# tank_motor_control.net
KiCad netlist of a schematic drawn in EAGLE
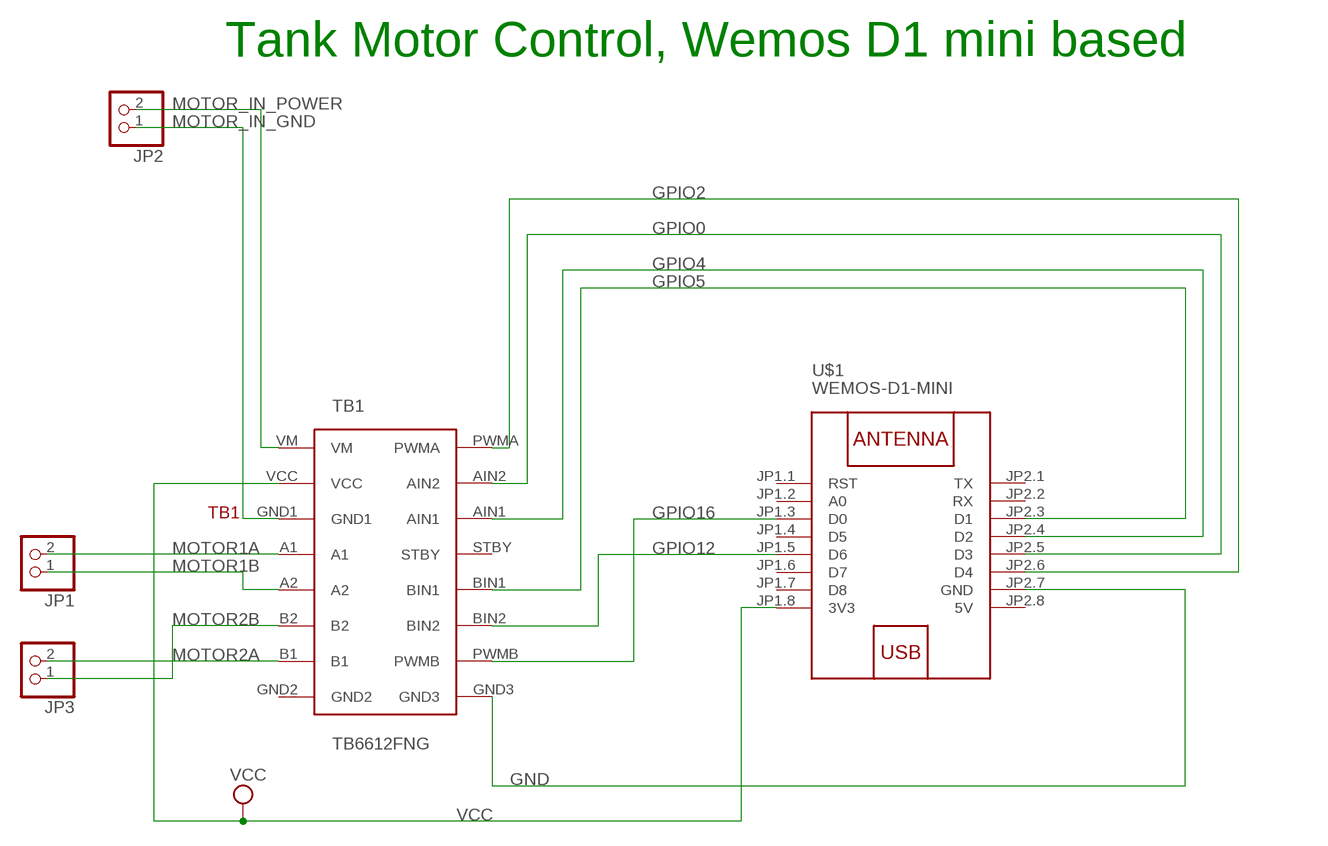
[diagram p0: schematic, sheet 1]

(export (version "E")
  (design (tool "Eeschema 10.0.6"))
  (components
    (comp (ref "JP1")
      (value "PINHD-1X2/90")
      (footprint "eagle-import:1X02_90")
      (libsource (lib "eagle-import") (part "PINHD-1X2/90"))
    )
    (comp (ref "JP2")
      (value "PINHD-1X2/90")
      (footprint "eagle-import:1X02_90")
      (libsource (lib "eagle-import") (part "PINHD-1X2/90"))
    )
    (comp (ref "JP3")
      (value "PINHD-1X2/90")
      (footprint "eagle-import:1X02_90")
      (libsource (lib "eagle-import") (part "PINHD-1X2/90"))
    )
    (comp (ref "TB1")
      (value "TB6612FNG")
      (footprint "eagle-import:TB6612FNG")
      (libsource (lib "eagle-import") (part "TB6612FNG"))
    )
    (comp (ref "U$1")
      (value "WEMOS-D1-MINI")
      (footprint "eagle-import:WEMOS-D1-MINI")
      (libsource (lib "eagle-import") (part "WEMOS-D1-MINI"))
    )
  )
  (nets
    (net (code "1") (name "/5V") (class "Default")
      (node (ref "U$1") (pin "JP2.8") (pinfunction "5V_JP2.8") (pintype "power_in"))
    )
    (net (code "2") (name "/GND") (class "Default")
      (node (ref "TB1") (pin "GND3") (pinfunction "GND3_GND3") (pintype "bidirectional"))
      (node (ref "U$1") (pin "JP2.7") (pinfunction "GND_JP2.7") (pintype "power_in"))
    )
    (net (code "3") (name "/GPIO0") (class "Default")
      (node (ref "TB1") (pin "AIN2") (pinfunction "AIN2_AIN2") (pintype "bidirectional"))
      (node (ref "U$1") (pin "JP2.5") (pinfunction "D3_JP2.5") (pintype "bidirectional"))
    )
    (net (code "4") (name "/GPIO2") (class "Default")
      (node (ref "TB1") (pin "PWMA") (pinfunction "PWMA_PWMA") (pintype "bidirectional"))
      (node (ref "U$1") (pin "JP2.6") (pinfunction "D4_JP2.6") (pintype "bidirectional"))
    )
    (net (code "5") (name "/GPIO4") (class "Default")
      (node (ref "TB1") (pin "AIN1") (pinfunction "AIN1_AIN1") (pintype "bidirectional"))
      (node (ref "U$1") (pin "JP2.4") (pinfunction "D2_JP2.4") (pintype "bidirectional"))
    )
    (net (code "6") (name "/GPIO5") (class "Default")
      (node (ref "TB1") (pin "BIN1") (pinfunction "BIN1_BIN1") (pintype "bidirectional"))
      (node (ref "U$1") (pin "JP2.3") (pinfunction "D1_JP2.3") (pintype "bidirectional"))
    )
    (net (code "7") (name "/GPIO12") (class "Default")
      (node (ref "TB1") (pin "BIN2") (pinfunction "BIN2_BIN2") (pintype "bidirectional"))
      (node (ref "U$1") (pin "JP1.5") (pinfunction "D6_JP1.5") (pintype "bidirectional"))
    )
    (net (code "8") (name "/GPIO16") (class "Default")
      (node (ref "TB1") (pin "PWMB") (pinfunction "PWMB_PWMB") (pintype "bidirectional"))
      (node (ref "U$1") (pin "JP1.3") (pinfunction "D0_JP1.3") (pintype "bidirectional"))
    )
    (net (code "9") (name "/MOTOR1A") (class "Default")
      (node (ref "JP1") (pin "2") (pinfunction "2_2") (pintype "passive"))
      (node (ref "TB1") (pin "A1") (pinfunction "A1_A1") (pintype "bidirectional"))
    )
    (net (code "10") (name "/MOTOR1B") (class "Default")
      (node (ref "JP1") (pin "1") (pinfunction "1_1") (pintype "passive"))
      (node (ref "TB1") (pin "A2") (pinfunction "A2_A2") (pintype "bidirectional"))
    )
    (net (code "11") (name "/MOTOR2A") (class "Default")
      (node (ref "JP3") (pin "2") (pinfunction "2_2") (pintype "passive"))
      (node (ref "TB1") (pin "B1") (pinfunction "B1_B1") (pintype "bidirectional"))
    )
    (net (code "12") (name "/MOTOR2B") (class "Default")
      (node (ref "JP3") (pin "1") (pinfunction "1_1") (pintype "passive"))
      (node (ref "TB1") (pin "B2") (pinfunction "B2_B2") (pintype "bidirectional"))
    )
    (net (code "13") (name "/MOTOR_IN_GND") (class "Default")
      (node (ref "JP2") (pin "1") (pinfunction "1_1") (pintype "passive"))
      (node (ref "TB1") (pin "GND1") (pinfunction "GND1_GND1") (pintype "bidirectional"))
    )
    (net (code "14") (name "/MOTOR_IN_POWER") (class "Default")
      (node (ref "JP2") (pin "2") (pinfunction "2_2") (pintype "passive"))
      (node (ref "TB1") (pin "VM") (pinfunction "VM_VM") (pintype "bidirectional"))
    )
    (net (code "15") (name "VCC") (class "Default")
      (node (ref "TB1") (pin "VCC") (pinfunction "VCC_VCC") (pintype "bidirectional"))
      (node (ref "U$1") (pin "JP1.8") (pinfunction "3V3_JP1.8") (pintype "power_in"))
    )
    (net (code "16") (name "unconnected-(TB1-PadGND2)") (class "Default")
      (node (ref "TB1") (pin "GND2") (pinfunction "GND2_GND2") (pintype "bidirectional"))
    )
    (net (code "17") (name "unconnected-(TB1-PadSTBY)") (class "Default")
      (node (ref "TB1") (pin "STBY") (pinfunction "STBY_STBY") (pintype "bidirectional"))
    )
    (net (code "18") (name "unconnected-(U$1-A0-PadJP1.2)") (class "Default")
      (node (ref "U$1") (pin "JP1.2") (pinfunction "A0_JP1.2") (pintype "bidirectional"))
    )
    (net (code "19") (name "unconnected-(U$1-D5-PadJP1.4)") (class "Default")
      (node (ref "U$1") (pin "JP1.4") (pinfunction "D5_JP1.4") (pintype "bidirectional"))
    )
    (net (code "20") (name "unconnected-(U$1-D7-PadJP1.6)") (class "Default")
      (node (ref "U$1") (pin "JP1.6") (pinfunction "D7_JP1.6") (pintype "bidirectional"))
    )
    (net (code "21") (name "unconnected-(U$1-D8-PadJP1.7)") (class "Default")
      (node (ref "U$1") (pin "JP1.7") (pinfunction "D8_JP1.7") (pintype "bidirectional"))
    )
    (net (code "22") (name "unconnected-(U$1-RST-PadJP1.1)") (class "Default")
      (node (ref "U$1") (pin "JP1.1") (pinfunction "RST_JP1.1") (pintype "bidirectional"))
    )
    (net (code "23") (name "unconnected-(U$1-RX-PadJP2.2)") (class "Default")
      (node (ref "U$1") (pin "JP2.2") (pinfunction "RX_JP2.2") (pintype "bidirectional"))
    )
    (net (code "24") (name "unconnected-(U$1-TX-PadJP2.1)") (class "Default")
      (node (ref "U$1") (pin "JP2.1") (pinfunction "TX_JP2.1") (pintype "bidirectional"))
    )
  )
)
